# MAPLE-CUN-V023.net
KiCad netlist of a schematic drawn in EAGLE
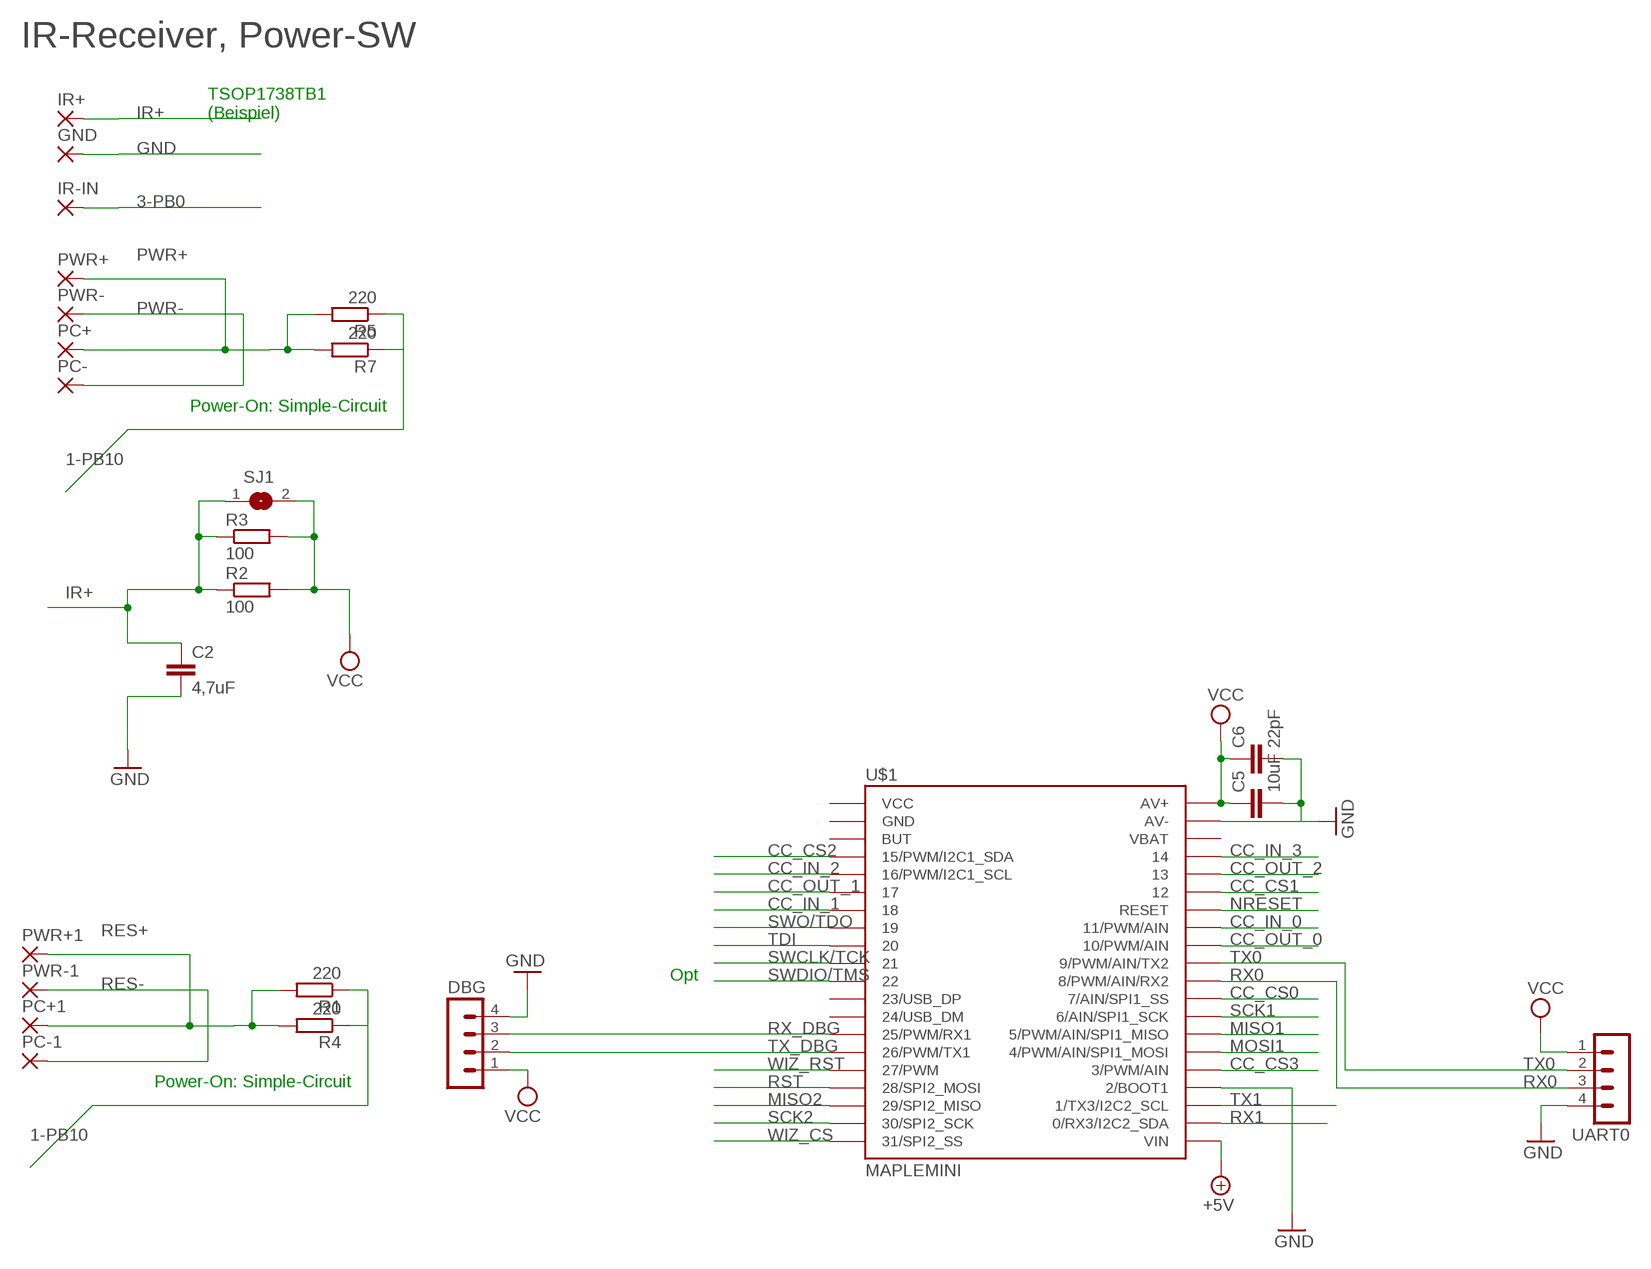
[diagram p0: schematic, sheet 1]

(export (version "E")
  (design (tool "Eeschema 10.0.6"))
  (components
    (comp (ref "C2")
      (value "4,7uF")
      (footprint "eagle-import:C1206K")
      (libsource (lib "eagle-import") (part "C-EUC1206K"))
    )
    (comp (ref "C5")
      (value "10uF")
      (footprint "eagle-import:C1210")
      (libsource (lib "eagle-import") (part "C-EUC1210"))
    )
    (comp (ref "C6")
      (value "22pF")
      (footprint "eagle-import:C0805")
      (libsource (lib "eagle-import") (part "C-EUC0805"))
    )
    (comp (ref "DBG")
      (value "MA04-1")
      (footprint "eagle-import:MA04-1")
      (libsource (lib "eagle-import") (part "MA04-1"))
    )
    (comp (ref "GND")
      (value "SMD2")
      (footprint "eagle-import:SMD1,27-2,54")
      (libsource (lib "eagle-import") (part "SMD2"))
    )
    (comp (ref "IR+")
      (value "SMD2")
      (footprint "eagle-import:SMD1,27-2,54")
      (libsource (lib "eagle-import") (part "SMD2"))
    )
    (comp (ref "IR-IN")
      (value "SMD2")
      (footprint "eagle-import:SMD1,27-2,54")
      (libsource (lib "eagle-import") (part "SMD2"))
    )
    (comp (ref "PC+")
      (value "SMD2")
      (footprint "eagle-import:SMD1,27-2,54")
      (libsource (lib "eagle-import") (part "SMD2"))
    )
    (comp (ref "PC+1")
      (value "SMD2")
      (footprint "eagle-import:SMD1,27-2,54")
      (libsource (lib "eagle-import") (part "SMD2"))
    )
    (comp (ref "PC-")
      (value "SMD2")
      (footprint "eagle-import:SMD1,27-2,54")
      (libsource (lib "eagle-import") (part "SMD2"))
    )
    (comp (ref "PC-1")
      (value "SMD2")
      (footprint "eagle-import:SMD1,27-2,54")
      (libsource (lib "eagle-import") (part "SMD2"))
    )
    (comp (ref "PWR+")
      (value "SMD2")
      (footprint "eagle-import:SMD1,27-2,54")
      (libsource (lib "eagle-import") (part "SMD2"))
    )
    (comp (ref "PWR+1")
      (value "SMD2")
      (footprint "eagle-import:SMD1,27-2,54")
      (libsource (lib "eagle-import") (part "SMD2"))
    )
    (comp (ref "PWR-")
      (value "SMD2")
      (footprint "eagle-import:SMD1,27-2,54")
      (libsource (lib "eagle-import") (part "SMD2"))
    )
    (comp (ref "PWR-1")
      (value "SMD2")
      (footprint "eagle-import:SMD1,27-2,54")
      (libsource (lib "eagle-import") (part "SMD2"))
    )
    (comp (ref "R1")
      (value "220")
      (footprint "eagle-import:0204_7")
      (libsource (lib "eagle-import") (part "R-EU_0204/7"))
    )
    (comp (ref "R2")
      (value "100")
      (footprint "eagle-import:0204_7")
      (libsource (lib "eagle-import") (part "R-EU_0204/7"))
    )
    (comp (ref "R3")
      (value "100")
      (footprint "eagle-import:R0805W")
      (libsource (lib "eagle-import") (part "R-EU_R0805W"))
    )
    (comp (ref "R4")
      (value "220")
      (footprint "eagle-import:R0805W")
      (libsource (lib "eagle-import") (part "R-EU_R0805W"))
    )
    (comp (ref "R5")
      (value "220")
      (footprint "eagle-import:0204_7")
      (libsource (lib "eagle-import") (part "R-EU_0204/7"))
    )
    (comp (ref "R7")
      (value "220")
      (footprint "eagle-import:R0805W")
      (libsource (lib "eagle-import") (part "R-EU_R0805W"))
    )
    (comp (ref "SJ1") (value "SJ") (footprint "eagle-import:SJ") (libsource (lib "eagle-import") (part "SJ")))
    (comp (ref "U$1")
      (value "MAPLEMINI")
      (footprint "eagle-import:20-DIP")
      (libsource (lib "eagle-import") (part "MAPLEMINI"))
    )
    (comp (ref "UART0")
      (value "MA04-1")
      (footprint "eagle-import:MA04-1")
      (libsource (lib "eagle-import") (part "MA04-1"))
    )
  )
  (nets
    (net (code "1") (name "+5V") (class "Default")
      (node (ref "U$1") (pin "21") (pinfunction "VIN_21") (pintype "bidirectional"))
    )
    (net (code "2") (name "/1-PB10") (class "Default")
      (node (ref "R1") (pin "1") (pinfunction "1_1") (pintype "passive"))
      (node (ref "R4") (pin "1") (pinfunction "1_1") (pintype "passive"))
      (node (ref "R5") (pin "1") (pinfunction "1_1") (pintype "passive"))
      (node (ref "R7") (pin "1") (pinfunction "1_1") (pintype "passive"))
    )
    (net (code "3") (name "/3-PB0") (class "Default")
      (node (ref "IR-IN") (pin "1") (pinfunction "P_1") (pintype "passive"))
    )
    (net (code "4") (name "/CC_CS0") (class "Default")
      (node (ref "U$1") (pin "29") (pinfunction "7/AIN/SPI1_SS_29") (pintype "bidirectional"))
    )
    (net (code "5") (name "/CC_CS1") (class "Default")
      (node (ref "U$1") (pin "35") (pinfunction "12_35") (pintype "bidirectional"))
    )
    (net (code "6") (name "/CC_CS2") (class "Default")
      (node (ref "U$1") (pin "4") (pinfunction "15/PWM/I2C1_SDA_4") (pintype "bidirectional"))
    )
    (net (code "7") (name "/CC_CS3") (class "Default")
      (node (ref "U$1") (pin "25") (pinfunction "3/PWM/AIN_25") (pintype "bidirectional"))
    )
    (net (code "8") (name "/CC_IN_0") (class "Default")
      (node (ref "U$1") (pin "33") (pinfunction "11/PWM/AIN_33") (pintype "bidirectional"))
    )
    (net (code "9") (name "/CC_IN_1") (class "Default")
      (node (ref "U$1") (pin "7") (pinfunction "18_7") (pintype "bidirectional"))
    )
    (net (code "10") (name "/CC_IN_2") (class "Default")
      (node (ref "U$1") (pin "5") (pinfunction "16/PWM/I2C1_SCL_5") (pintype "bidirectional"))
    )
    (net (code "11") (name "/CC_IN_3") (class "Default")
      (node (ref "U$1") (pin "37") (pinfunction "14_37") (pintype "bidirectional"))
    )
    (net (code "12") (name "/CC_OUT_0") (class "Default")
      (node (ref "U$1") (pin "32") (pinfunction "10/PWM/AIN_32") (pintype "bidirectional"))
    )
    (net (code "13") (name "/CC_OUT_1") (class "Default")
      (node (ref "U$1") (pin "6") (pinfunction "17_6") (pintype "bidirectional"))
    )
    (net (code "14") (name "/CC_OUT_2") (class "Default")
      (node (ref "U$1") (pin "36") (pinfunction "13_36") (pintype "bidirectional"))
    )
    (net (code "15") (name "/IR+") (class "Default")
      (node (ref "C2") (pin "1") (pinfunction "1_1") (pintype "passive"))
      (node (ref "IR+") (pin "1") (pinfunction "P_1") (pintype "passive"))
      (node (ref "R2") (pin "1") (pinfunction "1_1") (pintype "passive"))
      (node (ref "R3") (pin "1") (pinfunction "1_1") (pintype "passive"))
      (node (ref "SJ1") (pin "1") (pinfunction "1_1") (pintype "passive"))
    )
    (net (code "16") (name "/MISO1") (class "Default")
      (node (ref "U$1") (pin "27") (pinfunction "5/PWM/AIN/SPI1_MISO_27") (pintype "bidirectional"))
    )
    (net (code "17") (name "/MISO2") (class "Default")
      (node (ref "U$1") (pin "18") (pinfunction "29/SPI2_MISO_18") (pintype "bidirectional"))
    )
    (net (code "18") (name "/MOSI1") (class "Default")
      (node (ref "U$1") (pin "26") (pinfunction "4/PWM/AIN/SPI1_MOSI_26") (pintype "bidirectional"))
    )
    (net (code "19") (name "/NRESET") (class "Default")
      (node (ref "U$1") (pin "34") (pinfunction "RESET_34") (pintype "bidirectional"))
    )
    (net (code "20") (name "/PWR+") (class "Default")
      (node (ref "PC+") (pin "1") (pinfunction "P_1") (pintype "passive"))
      (node (ref "PWR+") (pin "1") (pinfunction "P_1") (pintype "passive"))
      (node (ref "R5") (pin "2") (pinfunction "2_2") (pintype "passive"))
      (node (ref "R7") (pin "2") (pinfunction "2_2") (pintype "passive"))
    )
    (net (code "21") (name "/PWR-") (class "Default")
      (node (ref "PC-") (pin "1") (pinfunction "P_1") (pintype "passive"))
      (node (ref "PWR-") (pin "1") (pinfunction "P_1") (pintype "passive"))
    )
    (net (code "22") (name "/RES+") (class "Default")
      (node (ref "PC+1") (pin "1") (pinfunction "P_1") (pintype "passive"))
      (node (ref "PWR+1") (pin "1") (pinfunction "P_1") (pintype "passive"))
      (node (ref "R1") (pin "2") (pinfunction "2_2") (pintype "passive"))
      (node (ref "R4") (pin "2") (pinfunction "2_2") (pintype "passive"))
    )
    (net (code "23") (name "/RES-") (class "Default")
      (node (ref "PC-1") (pin "1") (pinfunction "P_1") (pintype "passive"))
      (node (ref "PWR-1") (pin "1") (pinfunction "P_1") (pintype "passive"))
    )
    (net (code "24") (name "/RST") (class "Default")
      (node (ref "U$1") (pin "17") (pinfunction "28/SPI2_MOSI_17") (pintype "bidirectional"))
    )
    (net (code "25") (name "/RX0") (class "Default")
      (node (ref "U$1") (pin "30") (pinfunction "8/PWM/AIN/RX2_30") (pintype "bidirectional"))
      (node (ref "UART0") (pin "3") (pinfunction "3_3") (pintype "passive"))
    )
    (net (code "26") (name "/RX1") (class "Default")
      (node (ref "U$1") (pin "22") (pinfunction "0/RX3/I2C2_SDA_22") (pintype "bidirectional"))
    )
    (net (code "27") (name "/RX_DBG") (class "Default")
      (node (ref "DBG") (pin "3") (pinfunction "3_3") (pintype "passive"))
      (node (ref "U$1") (pin "14") (pinfunction "25/PWM/RX1_14") (pintype "bidirectional"))
    )
    (net (code "28") (name "/SCK1") (class "Default")
      (node (ref "U$1") (pin "28") (pinfunction "6/AIN/SPI1_SCK_28") (pintype "bidirectional"))
    )
    (net (code "29") (name "/SCK2") (class "Default")
      (node (ref "U$1") (pin "19") (pinfunction "30/SPI2_SCK_19") (pintype "bidirectional"))
    )
    (net (code "30") (name "/SWCLK{slash}TCK") (class "Default")
      (node (ref "U$1") (pin "10") (pinfunction "21_10") (pintype "bidirectional"))
    )
    (net (code "31") (name "/SWDIO{slash}TMS") (class "Default")
      (node (ref "U$1") (pin "11") (pinfunction "22_11") (pintype "bidirectional"))
    )
    (net (code "32") (name "/SWO{slash}TDO") (class "Default")
      (node (ref "U$1") (pin "8") (pinfunction "19_8") (pintype "bidirectional"))
    )
    (net (code "33") (name "/TDI") (class "Default")
      (node (ref "U$1") (pin "9") (pinfunction "20_9") (pintype "bidirectional"))
    )
    (net (code "34") (name "/TX0") (class "Default")
      (node (ref "U$1") (pin "31") (pinfunction "9/PWM/AIN/TX2_31") (pintype "bidirectional"))
      (node (ref "UART0") (pin "2") (pinfunction "2_2") (pintype "passive"))
    )
    (net (code "35") (name "/TX1") (class "Default")
      (node (ref "U$1") (pin "23") (pinfunction "1/TX3/I2C2_SCL_23") (pintype "bidirectional"))
    )
    (net (code "36") (name "/TX_DBG") (class "Default")
      (node (ref "DBG") (pin "2") (pinfunction "2_2") (pintype "passive"))
      (node (ref "U$1") (pin "15") (pinfunction "26/PWM/TX1_15") (pintype "bidirectional"))
    )
    (net (code "37") (name "/WIZ_CS") (class "Default")
      (node (ref "U$1") (pin "20") (pinfunction "31/SPI2_SS_20") (pintype "bidirectional"))
    )
    (net (code "38") (name "/WIZ_RST") (class "Default")
      (node (ref "U$1") (pin "16") (pinfunction "27/PWM_16") (pintype "bidirectional"))
    )
    (net (code "39") (name "GND") (class "Default")
      (node (ref "C2") (pin "2") (pinfunction "2_2") (pintype "passive"))
      (node (ref "C5") (pin "2") (pinfunction "2_2") (pintype "passive"))
      (node (ref "C6") (pin "2") (pinfunction "2_2") (pintype "passive"))
      (node (ref "DBG") (pin "4") (pinfunction "4_4") (pintype "passive"))
      (node (ref "GND") (pin "1") (pinfunction "P_1") (pintype "passive"))
      (node (ref "U$1") (pin "24") (pinfunction "2/BOOT1_24") (pintype "bidirectional"))
      (node (ref "U$1") (pin "39") (pinfunction "AV-_39") (pintype "bidirectional"))
      (node (ref "UART0") (pin "4") (pinfunction "4_4") (pintype "passive"))
    )
    (net (code "40") (name "VCC") (class "Default")
      (node (ref "C5") (pin "1") (pinfunction "1_1") (pintype "passive"))
      (node (ref "C6") (pin "1") (pinfunction "1_1") (pintype "passive"))
      (node (ref "DBG") (pin "1") (pinfunction "1_1") (pintype "passive"))
      (node (ref "R2") (pin "2") (pinfunction "2_2") (pintype "passive"))
      (node (ref "R3") (pin "2") (pinfunction "2_2") (pintype "passive"))
      (node (ref "SJ1") (pin "2") (pinfunction "2_2") (pintype "passive"))
      (node (ref "U$1") (pin "40") (pinfunction "AV+_40") (pintype "bidirectional"))
      (node (ref "UART0") (pin "1") (pinfunction "1_1") (pintype "passive"))
    )
    (net (code "41") (name "unconnected-(U$1-23{slash}USB_DP-Pad12)") (class "Default")
      (node (ref "U$1") (pin "12") (pinfunction "23/USB_DP_12") (pintype "bidirectional"))
    )
    (net (code "42") (name "unconnected-(U$1-24{slash}USB_DM-Pad13)") (class "Default")
      (node (ref "U$1") (pin "13") (pinfunction "24/USB_DM_13") (pintype "bidirectional"))
    )
    (net (code "43") (name "unconnected-(U$1-BUT-Pad3)") (class "Default")
      (node (ref "U$1") (pin "3") (pinfunction "BUT_3") (pintype "bidirectional"))
    )
    (net (code "44") (name "unconnected-(U$1-GND-Pad2)") (class "Default")
      (node (ref "U$1") (pin "2") (pinfunction "GND_2") (pintype "bidirectional"))
    )
    (net (code "45") (name "unconnected-(U$1-VBAT-Pad38)") (class "Default")
      (node (ref "U$1") (pin "38") (pinfunction "VBAT_38") (pintype "bidirectional"))
    )
    (net (code "46") (name "unconnected-(U$1-VCC-Pad1)") (class "Default")
      (node (ref "U$1") (pin "1") (pinfunction "VCC_1") (pintype "bidirectional"))
    )
  )
)
